# mml_mcu.net
KiCad netlist of a schematic drawn in EAGLE
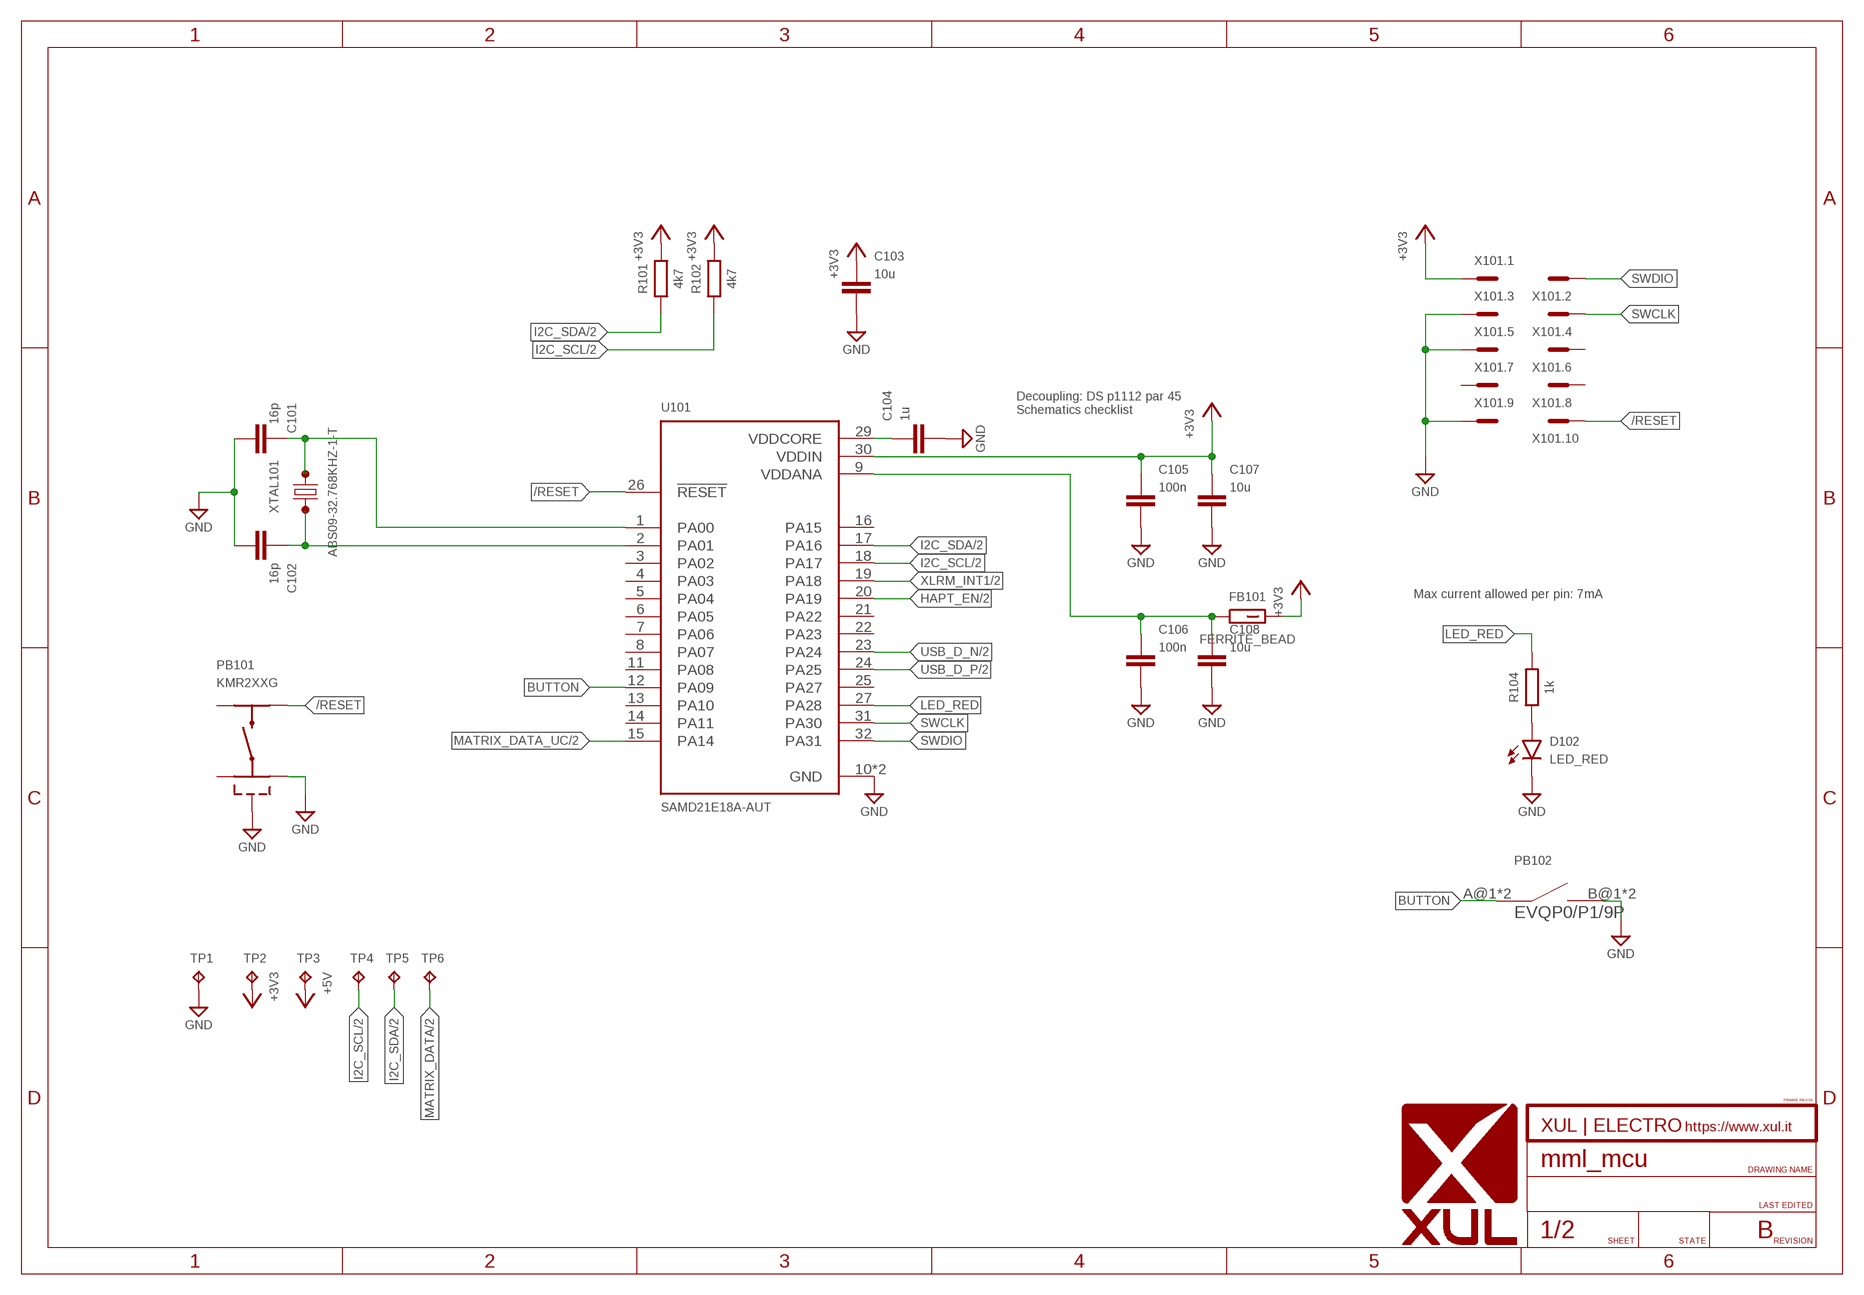
[diagram p0: schematic, sheet 1]
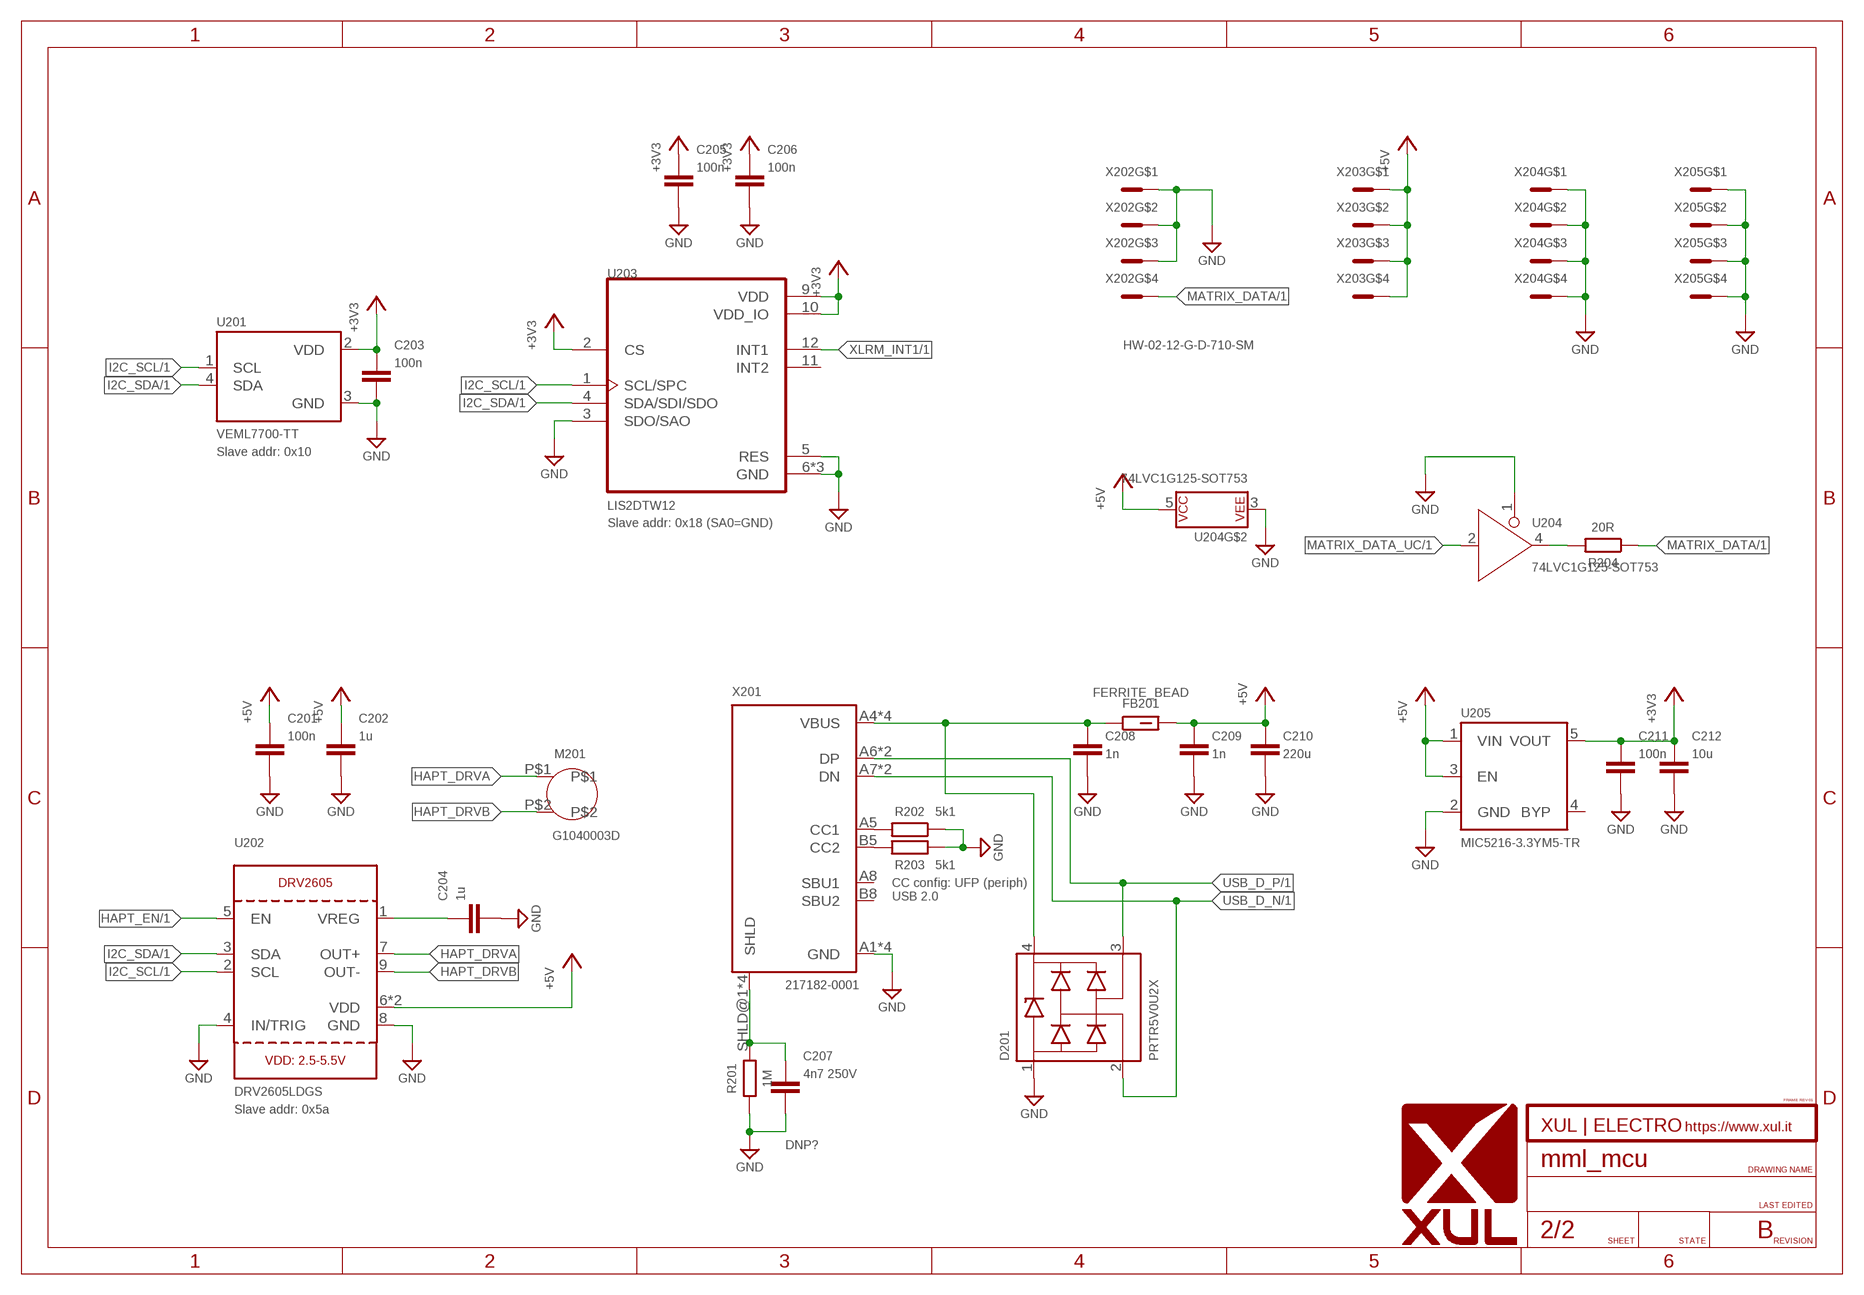
[diagram p1: schematic, sheet 2]

(export (version "E")
  (design (tool "Eeschema 10.0.6"))
  (components
    (comp (ref "C101")
      (value "16p")
      (footprint "eagle-import:CAPC1608X85")
      (libsource (lib "eagle-import") (part "CCHIP-0603(1608-METRIC)_"))
    )
    (comp (ref "C102")
      (value "16p")
      (footprint "eagle-import:CAPC1608X85")
      (libsource (lib "eagle-import") (part "CCHIP-0603(1608-METRIC)_"))
    )
    (comp (ref "C103")
      (value "10u")
      (footprint "eagle-import:CAPC2012X110")
      (libsource (lib "eagle-import") (part "CCHIP-0805(2012-METRIC)_"))
    )
    (comp (ref "C104")
      (value "1u")
      (footprint "eagle-import:CAPC1608X85")
      (libsource (lib "eagle-import") (part "CCHIP-0603(1608-METRIC)_"))
    )
    (comp (ref "C105")
      (value "100n")
      (footprint "eagle-import:CAPC1608X85")
      (libsource (lib "eagle-import") (part "CCHIP-0603(1608-METRIC)_"))
    )
    (comp (ref "C106")
      (value "100n")
      (footprint "eagle-import:CAPC1608X85")
      (libsource (lib "eagle-import") (part "CCHIP-0603(1608-METRIC)_"))
    )
    (comp (ref "C107")
      (value "10u")
      (footprint "eagle-import:CAPC2012X110")
      (libsource (lib "eagle-import") (part "CCHIP-0805(2012-METRIC)_"))
    )
    (comp (ref "C108")
      (value "10u")
      (footprint "eagle-import:CAPC2012X110")
      (libsource (lib "eagle-import") (part "CCHIP-0805(2012-METRIC)_"))
    )
    (comp (ref "D102")
      (value "LED_RED")
      (footprint "eagle-import:LEDC2012X110N_FLAT-R")
      (libsource (lib "eagle-import") (part "CHIP-FLAT-R_0805"))
    )
    (comp (ref "FB101")
      (value "FERRITE_BEAD")
      (footprint "eagle-import:BEADC1608X95N")
      (libsource (lib "eagle-import") (part "FBCHIP-0603(1608-METRIC)"))
    )
    (comp (ref "PB101")
      (value "KMR2XXG")
      (footprint "eagle-import:KMR2XXG")
      (libsource (lib "eagle-import") (part "KMR2XXG"))
    )
    (comp (ref "PB102")
      (value "EVQP0/P1/9P")
      (footprint "eagle-import:EVQP0_P1_9P")
      (libsource (lib "eagle-import") (part "EVQP0/P1/9P"))
    )
    (comp (ref "R101")
      (value "4k7")
      (footprint "eagle-import:RESC1608X60")
      (libsource (lib "eagle-import") (part "RCHIP-0603(1608-METRIC)_"))
    )
    (comp (ref "R102")
      (value "4k7")
      (footprint "eagle-import:RESC1608X60")
      (libsource (lib "eagle-import") (part "RCHIP-0603(1608-METRIC)_"))
    )
    (comp (ref "R104")
      (value "1k")
      (footprint "eagle-import:RESC1608X60")
      (libsource (lib "eagle-import") (part "RCHIP-0603(1608-METRIC)_"))
    )
    (comp (ref "TP1")
      (value "TPTP15R")
      (footprint "eagle-import:TP15R")
      (libsource (lib "eagle-import") (part "TPTP15R"))
    )
    (comp (ref "TP2")
      (value "TPTP15R")
      (footprint "eagle-import:TP15R")
      (libsource (lib "eagle-import") (part "TPTP15R"))
    )
    (comp (ref "TP3")
      (value "TPTP15R")
      (footprint "eagle-import:TP15R")
      (libsource (lib "eagle-import") (part "TPTP15R"))
    )
    (comp (ref "TP4")
      (value "TPTP15R")
      (footprint "eagle-import:TP15R")
      (libsource (lib "eagle-import") (part "TPTP15R"))
    )
    (comp (ref "TP5")
      (value "TPTP15R")
      (footprint "eagle-import:TP15R")
      (libsource (lib "eagle-import") (part "TPTP15R"))
    )
    (comp (ref "TP6")
      (value "TPTP15R")
      (footprint "eagle-import:TP15R")
      (libsource (lib "eagle-import") (part "TPTP15R"))
    )
    (comp (ref "U101")
      (value "SAMD21E18A-AUT")
      (footprint "eagle-import:QFP80P900X900X120-32N")
      (libsource (lib "eagle-import") (part "SAMD21E"))
    )
    (comp (ref "X101")
      (value "M50-3600542R")
      (footprint "eagle-import:M50-3600542R")
      (libsource (lib "eagle-import") (part "M50-3600542R"))
    )
    (comp (ref "XTAL101")
      (value "ABS09-32.768KHZ-1-T")
      (footprint "eagle-import:XTAL410X150X90")
      (libsource (lib "eagle-import") (part "CM415"))
    )
    (comp (ref "C201")
      (value "100n")
      (footprint "eagle-import:CAPC1608X85")
      (libsource (lib "eagle-import") (part "CCHIP-0603(1608-METRIC)_"))
    )
    (comp (ref "C202")
      (value "1u")
      (footprint "eagle-import:CAPC1608X85")
      (libsource (lib "eagle-import") (part "CCHIP-0603(1608-METRIC)_"))
    )
    (comp (ref "C203")
      (value "100n")
      (footprint "eagle-import:CAPC1608X85")
      (libsource (lib "eagle-import") (part "CCHIP-0603(1608-METRIC)_"))
    )
    (comp (ref "C204")
      (value "1u")
      (footprint "eagle-import:CAPC1608X85")
      (libsource (lib "eagle-import") (part "CCHIP-0603(1608-METRIC)_"))
    )
    (comp (ref "C205")
      (value "100n")
      (footprint "eagle-import:CAPC1608X85")
      (libsource (lib "eagle-import") (part "CCHIP-0603(1608-METRIC)_"))
    )
    (comp (ref "C206")
      (value "100n")
      (footprint "eagle-import:CAPC1608X85")
      (libsource (lib "eagle-import") (part "CCHIP-0603(1608-METRIC)_"))
    )
    (comp (ref "C207")
      (value "4n7 250V")
      (footprint "eagle-import:CAPC1608X85")
      (libsource (lib "eagle-import") (part "CCHIP-0603(1608-METRIC)_"))
    )
    (comp (ref "C208")
      (value "1n")
      (footprint "eagle-import:CAPC1608X85")
      (libsource (lib "eagle-import") (part "CCHIP-0603(1608-METRIC)_"))
    )
    (comp (ref "C209")
      (value "1n")
      (footprint "eagle-import:CAPC1608X85")
      (libsource (lib "eagle-import") (part "CCHIP-0603(1608-METRIC)_"))
    )
    (comp (ref "C210")
      (value "220u")
      (footprint "eagle-import:CAPC3216X135")
      (libsource (lib "eagle-import") (part "CCHIP-1206(3216-METRIC)_"))
    )
    (comp (ref "C211")
      (value "100n")
      (footprint "eagle-import:CAPC1608X85")
      (libsource (lib "eagle-import") (part "CCHIP-0603(1608-METRIC)_"))
    )
    (comp (ref "C212")
      (value "10u")
      (footprint "eagle-import:CAPC2012X110")
      (libsource (lib "eagle-import") (part "CCHIP-0805(2012-METRIC)_"))
    )
    (comp (ref "D201")
      (value "PRTR5V0U2X")
      (footprint "eagle-import:SOT190P230X110-4N")
      (libsource (lib "eagle-import") (part "PRTR5V0U2X"))
    )
    (comp (ref "FB201")
      (value "FERRITE_BEAD")
      (footprint "eagle-import:BEADC1608X95N")
      (libsource (lib "eagle-import") (part "FBCHIP-0603(1608-METRIC)"))
    )
    (comp (ref "M201")
      (value "G1040003D")
      (footprint "eagle-import:G1040003D")
      (libsource (lib "eagle-import") (part "G1040003D"))
    )
    (comp (ref "R201")
      (value "1M")
      (footprint "eagle-import:RESC1608X60")
      (libsource (lib "eagle-import") (part "RCHIP-0603(1608-METRIC)_"))
    )
    (comp (ref "R202")
      (value "5k1")
      (footprint "eagle-import:RESC1608X60")
      (libsource (lib "eagle-import") (part "RCHIP-0603(1608-METRIC)_"))
    )
    (comp (ref "R203")
      (value "5k1")
      (footprint "eagle-import:RESC1608X60")
      (libsource (lib "eagle-import") (part "RCHIP-0603(1608-METRIC)_"))
    )
    (comp (ref "R204")
      (value "20R")
      (footprint "eagle-import:RESC1608X60")
      (libsource (lib "eagle-import") (part "RCHIP-0603(1608-METRIC)_"))
    )
    (comp (ref "U201")
      (value "VEML7700-TT")
      (footprint "eagle-import:XDCR_VEML7700-TT")
      (fields (field (name "MF") "Vishay Semiconductor"))
      (libsource (lib "eagle-import") (part "VEML7700-TT"))
    )
    (comp (ref "U202")
      (value "DRV2605LDGS")
      (footprint "eagle-import:PSOP10")
      (fields (field (name "LCSC_PART") "C527464"))
      (libsource (lib "eagle-import") (part "DRV2605_SOP"))
    )
    (comp (ref "U203")
      (value "LIS2DTW12")
      (footprint "eagle-import:PQFN50P200X200100-12N")
      (fields
        (field (name "MF") "STMicroelectronics")
        (field (name "MP") "LIS2DH12TR")
        (field (name "LCSC_PART") "C110926")
      )
      (libsource (lib "eagle-import") (part "LIS2DH12TR"))
    )
    (comp (ref "U204")
      (value "74LVC1G125-SOT753")
      (footprint "eagle-import:SOT95P280X145-5N")
      (libsource (lib "eagle-import") (part "74LVC1G125-SOT753"))
    )
    (comp (ref "U205")
      (value "MIC5216-3.3YM5-TR")
      (footprint "eagle-import:SOT95P280X145-5N")
      (libsource (lib "eagle-import") (part "SPX3819SOT-23-5"))
    )
    (comp (ref "X201")
      (value "217182-0001")
      (footprint "eagle-import:217182-0001")
      (libsource (lib "eagle-import") (part "217182-0001"))
    )
    (comp (ref "X202")
      (value "HW-02-10-T-D-500-SM")
      (footprint "eagle-import:HW-02-10-T-D-500-SM")
      (libsource (lib "eagle-import") (part "HW-02-10-T-D-500-SM"))
    )
    (comp (ref "X203")
      (value "HW-02-10-T-D-500-SM")
      (footprint "eagle-import:HW-02-10-T-D-500-SM")
      (libsource (lib "eagle-import") (part "HW-02-10-T-D-500-SM"))
    )
    (comp (ref "X204")
      (value "HW-02-10-T-D-500-SM")
      (footprint "eagle-import:HW-02-10-T-D-500-SM")
      (libsource (lib "eagle-import") (part "HW-02-10-T-D-500-SM"))
    )
    (comp (ref "X205")
      (value "HW-02-10-T-D-500-SM")
      (footprint "eagle-import:HW-02-10-T-D-500-SM")
      (libsource (lib "eagle-import") (part "HW-02-10-T-D-500-SM"))
    )
  )
  (nets
    (net (code "1") (name "+3V3") (class "Default")
      (node (ref "C103") (pin "1") (pinfunction "1_1") (pintype "passive"))
      (node (ref "C105") (pin "1") (pinfunction "1_1") (pintype "passive"))
      (node (ref "C107") (pin "1") (pinfunction "1_1") (pintype "passive"))
      (node (ref "C203") (pin "1") (pinfunction "1_1") (pintype "passive"))
      (node (ref "C205") (pin "1") (pinfunction "1_1") (pintype "passive"))
      (node (ref "C206") (pin "1") (pinfunction "1_1") (pintype "passive"))
      (node (ref "C211") (pin "1") (pinfunction "1_1") (pintype "passive"))
      (node (ref "C212") (pin "1") (pinfunction "1_1") (pintype "passive"))
      (node (ref "FB101") (pin "2") (pinfunction "2_2") (pintype "passive"))
      (node (ref "R101") (pin "2") (pinfunction "2_2") (pintype "passive"))
      (node (ref "R102") (pin "2") (pinfunction "2_2") (pintype "passive"))
      (node (ref "TP2") (pin "TP") (pinfunction "TP_TP") (pintype "input"))
      (node (ref "U101") (pin "30") (pinfunction "VDDIN_30") (pintype "power_in"))
      (node (ref "U201") (pin "2") (pinfunction "VDD_2") (pintype "power_in"))
      (node (ref "U203") (pin "10") (pinfunction "VDD_IO_10") (pintype "power_in"))
      (node (ref "U203") (pin "2") (pinfunction "CS_2") (pintype "input"))
      (node (ref "U203") (pin "9") (pinfunction "VDD_9") (pintype "power_in"))
      (node (ref "U205") (pin "5") (pinfunction "VOUT_5") (pintype "bidirectional"))
      (node (ref "X101") (pin "1") (pinfunction "SK_1") (pintype "passive"))
    )
    (net (code "2") (name "+5V") (class "Default")
      (node (ref "C201") (pin "1") (pinfunction "1_1") (pintype "passive"))
      (node (ref "C202") (pin "1") (pinfunction "1_1") (pintype "passive"))
      (node (ref "C209") (pin "1") (pinfunction "1_1") (pintype "passive"))
      (node (ref "C210") (pin "1") (pinfunction "1_1") (pintype "passive"))
      (node (ref "FB201") (pin "2") (pinfunction "2_2") (pintype "passive"))
      (node (ref "TP3") (pin "TP") (pinfunction "TP_TP") (pintype "input"))
      (node (ref "U202") (pin "10") (pinfunction "VDD_10") (pintype "power_in"))
      (node (ref "U202") (pin "6") (pinfunction "VDD_6") (pintype "power_in"))
      (node (ref "U204") (pin "5") (pinfunction "P$V+_5") (pintype "bidirectional"))
      (node (ref "U205") (pin "1") (pinfunction "VIN_1") (pintype "bidirectional"))
      (node (ref "U205") (pin "3") (pinfunction "EN_3") (pintype "bidirectional"))
      (node (ref "X203") (pin "P$1") (pinfunction "SK_P$1") (pintype "passive"))
      (node (ref "X203") (pin "P$2") (pinfunction "SK_P$2") (pintype "passive"))
      (node (ref "X203") (pin "P$3") (pinfunction "SK_P$3") (pintype "passive"))
      (node (ref "X203") (pin "P$4") (pinfunction "SK_P$4") (pintype "passive"))
    )
    (net (code "3") (name "BUTTON") (class "Default")
      (node (ref "PB102") (pin "A@1") (pinfunction "A_A@1") (pintype "passive"))
      (node (ref "PB102") (pin "A@2") (pinfunction "A_A@2") (pintype "passive"))
      (node (ref "U101") (pin "12") (pinfunction "PA09_12") (pintype "bidirectional"))
    )
    (net (code "4") (name "GND") (class "Default")
      (node (ref "C101") (pin "2") (pinfunction "2_2") (pintype "passive"))
      (node (ref "C102") (pin "2") (pinfunction "2_2") (pintype "passive"))
      (node (ref "C103") (pin "2") (pinfunction "2_2") (pintype "passive"))
      (node (ref "C104") (pin "2") (pinfunction "2_2") (pintype "passive"))
      (node (ref "C105") (pin "2") (pinfunction "2_2") (pintype "passive"))
      (node (ref "C106") (pin "2") (pinfunction "2_2") (pintype "passive"))
      (node (ref "C107") (pin "2") (pinfunction "2_2") (pintype "passive"))
      (node (ref "C108") (pin "2") (pinfunction "2_2") (pintype "passive"))
      (node (ref "C201") (pin "2") (pinfunction "2_2") (pintype "passive"))
      (node (ref "C202") (pin "2") (pinfunction "2_2") (pintype "passive"))
      (node (ref "C203") (pin "2") (pinfunction "2_2") (pintype "passive"))
      (node (ref "C204") (pin "2") (pinfunction "2_2") (pintype "passive"))
      (node (ref "C205") (pin "2") (pinfunction "2_2") (pintype "passive"))
      (node (ref "C206") (pin "2") (pinfunction "2_2") (pintype "passive"))
      (node (ref "C207") (pin "2") (pinfunction "2_2") (pintype "passive"))
      (node (ref "C208") (pin "2") (pinfunction "2_2") (pintype "passive"))
      (node (ref "C209") (pin "2") (pinfunction "2_2") (pintype "passive"))
      (node (ref "C210") (pin "2") (pinfunction "2_2") (pintype "passive"))
      (node (ref "C211") (pin "2") (pinfunction "2_2") (pintype "passive"))
      (node (ref "C212") (pin "2") (pinfunction "2_2") (pintype "passive"))
      (node (ref "D102") (pin "C") (pinfunction "C_C") (pintype "passive"))
      (node (ref "D201") (pin "1") (pinfunction "1_1") (pintype "bidirectional"))
      (node (ref "PB101") (pin "2") (pinfunction "2_2") (pintype "passive"))
      (node (ref "PB101") (pin "5") (pinfunction "5_5") (pintype "passive"))
      (node (ref "PB102") (pin "B@1") (pinfunction "B_B@1") (pintype "passive"))
      (node (ref "PB102") (pin "B@2") (pinfunction "B_B@2") (pintype "passive"))
      (node (ref "R201") (pin "1") (pinfunction "1_1") (pintype "passive"))
      (node (ref "R202") (pin "1") (pinfunction "1_1") (pintype "passive"))
      (node (ref "R203") (pin "1") (pinfunction "1_1") (pintype "passive"))
      (node (ref "TP1") (pin "TP") (pinfunction "TP_TP") (pintype "input"))
      (node (ref "U101") (pin "10") (pinfunction "GND_10") (pintype "power_in"))
      (node (ref "U101") (pin "28") (pinfunction "GND_28") (pintype "power_in"))
      (node (ref "U201") (pin "3") (pinfunction "GND_3") (pintype "power_in"))
      (node (ref "U202") (pin "4") (pinfunction "IN/TRIG_4") (pintype "input"))
      (node (ref "U202") (pin "8") (pinfunction "GND_8") (pintype "power_in"))
      (node (ref "U203") (pin "3") (pinfunction "SDO/SAO_3") (pintype "bidirectional"))
      (node (ref "U203") (pin "5") (pinfunction "RES_5") (pintype "power_in"))
      (node (ref "U203") (pin "6") (pinfunction "GND_6") (pintype "power_in"))
      (node (ref "U203") (pin "7") (pinfunction "GND_7") (pintype "power_in"))
      (node (ref "U203") (pin "8") (pinfunction "GND_8") (pintype "power_in"))
      (node (ref "U204") (pin "1") (pinfunction "/OE_1") (pintype "input"))
      (node (ref "U204") (pin "3") (pinfunction "P$V-_3") (pintype "bidirectional"))
      (node (ref "U205") (pin "2") (pinfunction "GND_2") (pintype "bidirectional"))
      (node (ref "X101") (pin "3") (pinfunction "SK_3") (pintype "passive"))
      (node (ref "X101") (pin "5") (pinfunction "SK_5") (pintype "passive"))
      (node (ref "X101") (pin "9") (pinfunction "SK_9") (pintype "passive"))
      (node (ref "X201") (pin "A1") (pinfunction "GND_A1") (pintype "bidirectional"))
      (node (ref "X201") (pin "A12") (pinfunction "GND_A12") (pintype "bidirectional"))
      (node (ref "X201") (pin "B1") (pinfunction "GND_B1") (pintype "bidirectional"))
      (node (ref "X201") (pin "B12") (pinfunction "GND_B12") (pintype "bidirectional"))
      (node (ref "X202") (pin "P$1") (pinfunction "SK_P$1") (pintype "passive"))
      (node (ref "X202") (pin "P$2") (pinfunction "SK_P$2") (pintype "passive"))
      (node (ref "X202") (pin "P$3") (pinfunction "SK_P$3") (pintype "passive"))
      (node (ref "X204") (pin "P$1") (pinfunction "SK_P$1") (pintype "passive"))
      (node (ref "X204") (pin "P$2") (pinfunction "SK_P$2") (pintype "passive"))
      (node (ref "X204") (pin "P$3") (pinfunction "SK_P$3") (pintype "passive"))
      (node (ref "X204") (pin "P$4") (pinfunction "SK_P$4") (pintype "passive"))
      (node (ref "X205") (pin "P$1") (pinfunction "SK_P$1") (pintype "passive"))
      (node (ref "X205") (pin "P$2") (pinfunction "SK_P$2") (pintype "passive"))
      (node (ref "X205") (pin "P$3") (pinfunction "SK_P$3") (pintype "passive"))
      (node (ref "X205") (pin "P$4") (pinfunction "SK_P$4") (pintype "passive"))
    )
    (net (code "5") (name "HAPT_DRVA") (class "Default")
      (node (ref "M201") (pin "P$1") (pinfunction "P$1_P$1") (pintype "passive"))
      (node (ref "U202") (pin "7") (pinfunction "OUT+_7") (pintype "output"))
    )
    (net (code "6") (name "HAPT_DRVB") (class "Default")
      (node (ref "M201") (pin "P$2") (pinfunction "P$2_P$2") (pintype "passive"))
      (node (ref "U202") (pin "9") (pinfunction "OUT-_9") (pintype "output"))
    )
    (net (code "7") (name "HAPT_EN") (class "Default")
      (node (ref "U101") (pin "20") (pinfunction "PA19_20") (pintype "bidirectional"))
      (node (ref "U202") (pin "5") (pinfunction "EN_5") (pintype "input"))
    )
    (net (code "8") (name "I2C_SCL") (class "Default")
      (node (ref "R102") (pin "1") (pinfunction "1_1") (pintype "passive"))
      (node (ref "TP4") (pin "TP") (pinfunction "TP_TP") (pintype "input"))
      (node (ref "U101") (pin "18") (pinfunction "PA17_18") (pintype "bidirectional"))
      (node (ref "U201") (pin "1") (pinfunction "SCL_1") (pintype "input"))
      (node (ref "U202") (pin "2") (pinfunction "SCL_2") (pintype "input"))
      (node (ref "U203") (pin "1") (pinfunction "SCL/SPC_1") (pintype "bidirectional"))
    )
    (net (code "9") (name "I2C_SDA") (class "Default")
      (node (ref "R101") (pin "1") (pinfunction "1_1") (pintype "passive"))
      (node (ref "TP5") (pin "TP") (pinfunction "TP_TP") (pintype "input"))
      (node (ref "U101") (pin "17") (pinfunction "PA16_17") (pintype "bidirectional"))
      (node (ref "U201") (pin "4") (pinfunction "SDA_4") (pintype "bidirectional"))
      (node (ref "U202") (pin "3") (pinfunction "SDA_3") (pintype "bidirectional"))
      (node (ref "U203") (pin "4") (pinfunction "SDA/SDI/SDO_4") (pintype "bidirectional"))
    )
    (net (code "10") (name "LED_RED") (class "Default")
      (node (ref "R104") (pin "2") (pinfunction "2_2") (pintype "passive"))
      (node (ref "U101") (pin "27") (pinfunction "PA28_27") (pintype "bidirectional"))
    )
    (net (code "11") (name "MATRIX_DATA") (class "Default")
      (node (ref "R204") (pin "1") (pinfunction "1_1") (pintype "passive"))
      (node (ref "TP6") (pin "TP") (pinfunction "TP_TP") (pintype "input"))
      (node (ref "X202") (pin "P$4") (pinfunction "SK_P$4") (pintype "passive"))
    )
    (net (code "12") (name "MATRIX_DATA_UC") (class "Default")
      (node (ref "U101") (pin "15") (pinfunction "PA14_15") (pintype "bidirectional"))
      (node (ref "U204") (pin "2") (pinfunction "A_2") (pintype "input"))
    )
    (net (code "13") (name "Net-(C207-Pad1)") (class "Default")
      (node (ref "C207") (pin "1") (pinfunction "1_1") (pintype "passive"))
      (node (ref "R201") (pin "2") (pinfunction "2_2") (pintype "passive"))
      (node (ref "X201") (pin "SHLD@1") (pinfunction "SHLD_SHLD@1") (pintype "bidirectional"))
      (node (ref "X201") (pin "SHLD@2") (pinfunction "SHLD_SHLD@2") (pintype "bidirectional"))
      (node (ref "X201") (pin "SHLD@3") (pinfunction "SHLD_SHLD@3") (pintype "bidirectional"))
      (node (ref "X201") (pin "SHLD@4") (pinfunction "SHLD_SHLD@4") (pintype "bidirectional"))
    )
    (net (code "14") (name "Net-(C208-Pad1)") (class "Default")
      (node (ref "C208") (pin "1") (pinfunction "1_1") (pintype "passive"))
      (node (ref "D201") (pin "4") (pinfunction "4_4") (pintype "bidirectional"))
      (node (ref "FB201") (pin "1") (pinfunction "1_1") (pintype "passive"))
      (node (ref "X201") (pin "A4") (pinfunction "VBUS_A4") (pintype "bidirectional"))
      (node (ref "X201") (pin "A9") (pinfunction "VBUS_A9") (pintype "bidirectional"))
      (node (ref "X201") (pin "B4") (pinfunction "VBUS_B4") (pintype "bidirectional"))
      (node (ref "X201") (pin "B9") (pinfunction "VBUS_B9") (pintype "bidirectional"))
    )
    (net (code "15") (name "Net-(D102-PadA)") (class "Default")
      (node (ref "D102") (pin "A") (pinfunction "A_A") (pintype "passive"))
      (node (ref "R104") (pin "1") (pinfunction "1_1") (pintype "passive"))
    )
    (net (code "16") (name "Net-(U101-PA00)") (class "Default")
      (node (ref "C101") (pin "1") (pinfunction "1_1") (pintype "passive"))
      (node (ref "U101") (pin "1") (pinfunction "PA00_1") (pintype "bidirectional"))
      (node (ref "XTAL101") (pin "1") (pinfunction "A_1") (pintype "passive"))
    )
    (net (code "17") (name "Net-(U101-PA01)") (class "Default")
      (node (ref "C102") (pin "1") (pinfunction "1_1") (pintype "passive"))
      (node (ref "U101") (pin "2") (pinfunction "PA01_2") (pintype "bidirectional"))
      (node (ref "XTAL101") (pin "2") (pinfunction "B_2") (pintype "passive"))
    )
    (net (code "18") (name "Net-(U101-VDDANA)") (class "Default")
      (node (ref "C106") (pin "1") (pinfunction "1_1") (pintype "passive"))
      (node (ref "C108") (pin "1") (pinfunction "1_1") (pintype "passive"))
      (node (ref "FB101") (pin "1") (pinfunction "1_1") (pintype "passive"))
      (node (ref "U101") (pin "9") (pinfunction "VDDANA_9") (pintype "power_in"))
    )
    (net (code "19") (name "Net-(U101-VDDCORE)") (class "Default")
      (node (ref "C104") (pin "1") (pinfunction "1_1") (pintype "passive"))
      (node (ref "U101") (pin "29") (pinfunction "VDDCORE_29") (pintype "power_in"))
    )
    (net (code "20") (name "Net-(U202-VREG)") (class "Default")
      (node (ref "C204") (pin "1") (pinfunction "1_1") (pintype "passive"))
      (node (ref "U202") (pin "1") (pinfunction "VREG_1") (pintype "output"))
    )
    (net (code "21") (name "Net-(U204A-Y)") (class "Default")
      (node (ref "R204") (pin "2") (pinfunction "2_2") (pintype "passive"))
      (node (ref "U204") (pin "4") (pinfunction "Y_4") (pintype "tri_state"))
    )
    (net (code "22") (name "Net-(X201-CC1)") (class "Default")
      (node (ref "R202") (pin "2") (pinfunction "2_2") (pintype "passive"))
      (node (ref "X201") (pin "A5") (pinfunction "CC1_A5") (pintype "bidirectional"))
    )
    (net (code "23") (name "Net-(X201-CC2)") (class "Default")
      (node (ref "R203") (pin "2") (pinfunction "2_2") (pintype "passive"))
      (node (ref "X201") (pin "B5") (pinfunction "CC2_B5") (pintype "bidirectional"))
    )
    (net (code "24") (name "SWCLK") (class "Default")
      (node (ref "U101") (pin "31") (pinfunction "PA30_31") (pintype "bidirectional"))
      (node (ref "X101") (pin "4") (pinfunction "SK_4") (pintype "passive"))
    )
    (net (code "25") (name "SWDIO") (class "Default")
      (node (ref "U101") (pin "32") (pinfunction "PA31_32") (pintype "bidirectional"))
      (node (ref "X101") (pin "2") (pinfunction "SK_2") (pintype "passive"))
    )
    (net (code "26") (name "USB_D_N") (class "Default")
      (node (ref "D201") (pin "2") (pinfunction "2_2") (pintype "bidirectional"))
      (node (ref "U101") (pin "23") (pinfunction "PA24_23") (pintype "bidirectional"))
      (node (ref "X201") (pin "A7") (pinfunction "DN_A7") (pintype "bidirectional"))
      (node (ref "X201") (pin "B7") (pinfunction "DN_B7") (pintype "bidirectional"))
    )
    (net (code "27") (name "USB_D_P") (class "Default")
      (node (ref "D201") (pin "3") (pinfunction "3_3") (pintype "bidirectional"))
      (node (ref "U101") (pin "24") (pinfunction "PA25_24") (pintype "bidirectional"))
      (node (ref "X201") (pin "A6") (pinfunction "DP_A6") (pintype "bidirectional"))
      (node (ref "X201") (pin "B6") (pinfunction "DP_B6") (pintype "bidirectional"))
    )
    (net (code "28") (name "XLRM_INT1") (class "Default")
      (node (ref "U101") (pin "19") (pinfunction "PA18_19") (pintype "bidirectional"))
      (node (ref "U203") (pin "12") (pinfunction "INT1_12") (pintype "output"))
    )
    (net (code "29") (name "unconnected-(PB101-Pad3)") (class "Default")
      (node (ref "PB101") (pin "3") (pinfunction "3_3") (pintype "passive"))
    )
    (net (code "30") (name "unconnected-(PB101-Pad4)") (class "Default")
      (node (ref "PB101") (pin "4") (pinfunction "4_4") (pintype "passive"))
    )
    (net (code "31") (name "unconnected-(U101-PA02-Pad3)") (class "Default")
      (node (ref "U101") (pin "3") (pinfunction "PA02_3") (pintype "bidirectional"))
    )
    (net (code "32") (name "unconnected-(U101-PA03-Pad4)") (class "Default")
      (node (ref "U101") (pin "4") (pinfunction "PA03_4") (pintype "bidirectional"))
    )
    (net (code "33") (name "unconnected-(U101-PA04-Pad5)") (class "Default")
      (node (ref "U101") (pin "5") (pinfunction "PA04_5") (pintype "bidirectional"))
    )
    (net (code "34") (name "unconnected-(U101-PA05-Pad6)") (class "Default")
      (node (ref "U101") (pin "6") (pinfunction "PA05_6") (pintype "bidirectional"))
    )
    (net (code "35") (name "unconnected-(U101-PA06-Pad7)") (class "Default")
      (node (ref "U101") (pin "7") (pinfunction "PA06_7") (pintype "bidirectional"))
    )
    (net (code "36") (name "unconnected-(U101-PA07-Pad8)") (class "Default")
      (node (ref "U101") (pin "8") (pinfunction "PA07_8") (pintype "bidirectional"))
    )
    (net (code "37") (name "unconnected-(U101-PA08-Pad11)") (class "Default")
      (node (ref "U101") (pin "11") (pinfunction "PA08_11") (pintype "bidirectional"))
    )
    (net (code "38") (name "unconnected-(U101-PA10-Pad13)") (class "Default")
      (node (ref "U101") (pin "13") (pinfunction "PA10_13") (pintype "bidirectional"))
    )
    (net (code "39") (name "unconnected-(U101-PA11-Pad14)") (class "Default")
      (node (ref "U101") (pin "14") (pinfunction "PA11_14") (pintype "bidirectional"))
    )
    (net (code "40") (name "unconnected-(U101-PA15-Pad16)") (class "Default")
      (node (ref "U101") (pin "16") (pinfunction "PA15_16") (pintype "bidirectional"))
    )
    (net (code "41") (name "unconnected-(U101-PA22-Pad21)") (class "Default")
      (node (ref "U101") (pin "21") (pinfunction "PA22_21") (pintype "bidirectional"))
    )
    (net (code "42") (name "unconnected-(U101-PA23-Pad22)") (class "Default")
      (node (ref "U101") (pin "22") (pinfunction "PA23_22") (pintype "bidirectional"))
    )
    (net (code "43") (name "unconnected-(U101-PA27-Pad25)") (class "Default")
      (node (ref "U101") (pin "25") (pinfunction "PA27_25") (pintype "bidirectional"))
    )
    (net (code "44") (name "unconnected-(U203-INT2-Pad11)") (class "Default")
      (node (ref "U203") (pin "11") (pinfunction "INT2_11") (pintype "output"))
    )
    (net (code "45") (name "unconnected-(U205-BYP-Pad4)") (class "Default")
      (node (ref "U205") (pin "4") (pinfunction "BYP_4") (pintype "bidirectional"))
    )
    (net (code "46") (name "unconnected-(X101G-SK-Pad6)") (class "Default")
      (node (ref "X101") (pin "6") (pinfunction "SK_6") (pintype "passive"))
    )
    (net (code "47") (name "unconnected-(X101H-SK-Pad7)") (class "Default")
      (node (ref "X101") (pin "7") (pinfunction "SK_7") (pintype "passive"))
    )
    (net (code "48") (name "unconnected-(X101I-SK-Pad8)") (class "Default")
      (node (ref "X101") (pin "8") (pinfunction "SK_8") (pintype "passive"))
    )
    (net (code "49") (name "unconnected-(X201-SBU1-PadA8)") (class "Default")
      (node (ref "X201") (pin "A8") (pinfunction "SBU1_A8") (pintype "bidirectional"))
    )
    (net (code "50") (name "unconnected-(X201-SBU2-PadB8)") (class "Default")
      (node (ref "X201") (pin "B8") (pinfunction "SBU2_B8") (pintype "bidirectional"))
    )
    (net (code "51") (name "{slash}RESET") (class "Default")
      (node (ref "PB101") (pin "1") (pinfunction "1_1") (pintype "passive"))
      (node (ref "U101") (pin "26") (pinfunction "~{RESET}_26") (pintype "input"))
      (node (ref "X101") (pin "10") (pinfunction "SK_10") (pintype "passive"))
    )
  )
)
